# design.net
KiCad netlist of a schematic drawn in Altium Designer
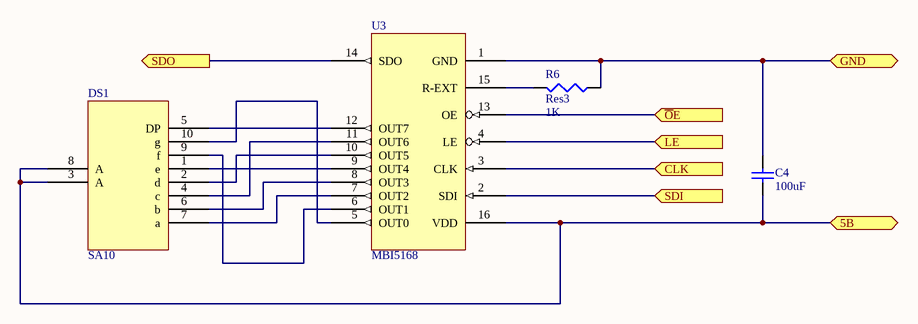
[diagram p0: Индикатор с драйвером.SchDoc]

(export (version "E")
  (design (tool "Eeschema 10.0.6"))
  (components
    (comp (ref "C4")
      (value "100uF")
      (footprint "CAPC1608L")
      (description "Capacitor (Semiconductor SIM Model)")
      (fields (field (name "Comment") "Cap Semi") (field (name "PUBLISHER") "Altium Limited"))
      (libsource (lib "Miscellaneous Devices") (part "Cap Semi"))
    )
    (comp (ref "DS1")
      (value "SA10")
      (footprint "SA10-21_SMD")
      (description "KingBright, SA10-21GWA")
      (libsource (lib "Integrated_Library1") (part "SA10-21GWA"))
    )
    (comp (ref "R6")
      (value "Res3")
      (footprint "RESC1608L")
      (description "Resistor")
      (fields (field (name "ALTIUM_VALUE") "1K") (field (name "PUBLISHER") "Altium Limited"))
      (libsource (lib "Miscellaneous Devices") (part "Res3"))
    )
    (comp (ref "U3")
      (value "MBI5168")
      (footprint "SO-16_M")
      (description "Macroblock, 8-bit Constant Current LED Sink Driver")
      (libsource (lib "LibX") (part "MBI5168"))
    )
  )
  (nets
    (net (code "1") (name "/5В") (class "Default")
      (node (ref "C4") (pin "2") (pinfunction "2_2") (pintype "passive"))
      (node (ref "DS1") (pin "3") (pinfunction "A_3") (pintype "passive"))
      (node (ref "DS1") (pin "8") (pinfunction "A_8") (pintype "passive"))
      (node (ref "U3") (pin "16") (pinfunction "VDD_16") (pintype "power_in"))
    )
    (net (code "2") (name "/CLK") (class "Default")
      (node (ref "U3") (pin "3") (pinfunction "CLK_3") (pintype "input"))
    )
    (net (code "3") (name "/GND") (class "Default")
      (node (ref "C4") (pin "1") (pinfunction "1_1") (pintype "passive"))
      (node (ref "R6") (pin "1") (pinfunction "1_1") (pintype "passive"))
      (node (ref "U3") (pin "1") (pinfunction "GND_1") (pintype "power_in"))
    )
    (net (code "4") (name "/LE") (class "Default")
      (node (ref "U3") (pin "4") (pinfunction "LE_4") (pintype "input"))
    )
    (net (code "5") (name "/SDI") (class "Default")
      (node (ref "U3") (pin "2") (pinfunction "SDI_2") (pintype "input"))
    )
    (net (code "6") (name "/SDO") (class "Default")
      (node (ref "U3") (pin "14") (pinfunction "SDO_14") (pintype "output"))
    )
    (net (code "7") (name "/~{O}E") (class "Default")
      (node (ref "U3") (pin "13") (pinfunction "OE_13") (pintype "input"))
    )
    (net (code "8") (name "Net-(DS1-DP)") (class "Default")
      (node (ref "DS1") (pin "5") (pinfunction "DP_5") (pintype "passive"))
      (node (ref "U3") (pin "12") (pinfunction "OUT7_12") (pintype "output"))
    )
    (net (code "9") (name "Net-(DS1-a)") (class "Default")
      (node (ref "DS1") (pin "7") (pinfunction "a_7") (pintype "passive"))
      (node (ref "U3") (pin "7") (pinfunction "OUT2_7") (pintype "output"))
    )
    (net (code "10") (name "Net-(DS1-b)") (class "Default")
      (node (ref "DS1") (pin "6") (pinfunction "b_6") (pintype "passive"))
      (node (ref "U3") (pin "8") (pinfunction "OUT3_8") (pintype "output"))
    )
    (net (code "11") (name "Net-(DS1-c)") (class "Default")
      (node (ref "DS1") (pin "4") (pinfunction "c_4") (pintype "passive"))
      (node (ref "U3") (pin "11") (pinfunction "OUT6_11") (pintype "output"))
    )
    (net (code "12") (name "Net-(DS1-d)") (class "Default")
      (node (ref "DS1") (pin "2") (pinfunction "d_2") (pintype "passive"))
      (node (ref "U3") (pin "10") (pinfunction "OUT5_10") (pintype "output"))
    )
    (net (code "13") (name "Net-(DS1-e)") (class "Default")
      (node (ref "DS1") (pin "1") (pinfunction "e_1") (pintype "passive"))
      (node (ref "U3") (pin "9") (pinfunction "OUT4_9") (pintype "output"))
    )
    (net (code "14") (name "Net-(DS1-f)") (class "Default")
      (node (ref "DS1") (pin "9") (pinfunction "f_9") (pintype "passive"))
      (node (ref "U3") (pin "6") (pinfunction "OUT1_6") (pintype "output"))
    )
    (net (code "15") (name "Net-(DS1-g)") (class "Default")
      (node (ref "DS1") (pin "10") (pinfunction "g_10") (pintype "passive"))
      (node (ref "U3") (pin "5") (pinfunction "OUT0_5") (pintype "output"))
    )
    (net (code "16") (name "Net-(U3-R-EXT)") (class "Default")
      (node (ref "R6") (pin "2") (pinfunction "2_2") (pintype "passive"))
      (node (ref "U3") (pin "15") (pinfunction "R-EXT_15") (pintype "passive"))
    )
  )
)
